# Relay_Output.net
KiCad netlist of a schematic drawn in Altium Designer
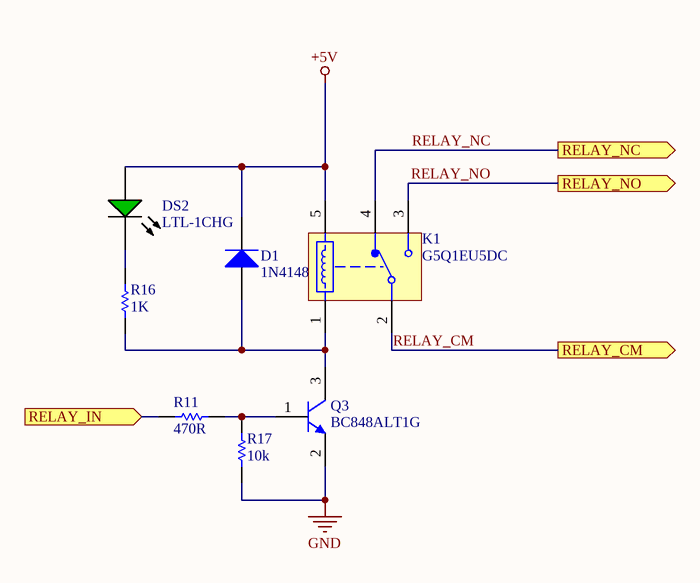
[diagram p0: Relay Output.SchDoc]

(export (version "E")
  (design (tool "Eeschema 10.0.6"))
  (components
    (comp (ref "D1")
      (value "1N4148WT")
      (footprint "FAIR-SOD-523F-2_V")
      (description "High Conductance Fast Switching Diode, 75 V, -55 to 150 degC, 2-Pin SOD523F, RoHS")
      (fields (field (name "MANUFACTURER") "Fairchild Semiconductor"))
      (libsource (lib "Altium Content Vault") (part "FAIR-D_K1A2-2"))
    )
    (comp (ref "DS2")
      (value "LTL-1CHG")
      (footprint "LTST-LTL-1CHG-2")
      (description "LITE-ON Electronic, INC, 120 mA, 100 mW, 5 V, -55 to 100 degC, 2-Pin THD, RoHS, Bulk")
      (libsource (lib "Altium Content Vault") (part "LED_GREEN_A1K2-2"))
    )
    (comp (ref "K1")
      (value "G5Q1EU5DC")
      (footprint "G5Q1EU5DC")
      (description "OMRON - G5Q-1EU 5DC - RELAY, SPDT, 250VAC, 30VDC, 10A")
      (libsource (lib "cpd") (part "G5Q1EU5DC"))
    )
    (comp (ref "Q3")
      (value "BC848ALT1G")
      (footprint "ONSC-SOT-23-3-318-08_V")
      (description "General Purpose Transistor, NPN Silicon, 3-Pin SOT-23, Pb-Free, Tape and Reel")
      (fields (field (name "MANUFACTURER") "On Semiconductor"))
      (libsource (lib "Altium Content Vault") (part "ONSC-NPN-B1E2C3-3"))
    )
    (comp (ref "R11")
      (value "470R")
      (footprint "RESC0603(1608)_M")
      (description "470R 0.1W 1% 0603 (1608 Metric)  SMD")
      (fields (field (name "POWER") "0.1 W") (field (name "TOLERANCE") "1 %"))
      (libsource (lib "Altium Content Vault") (part "RES"))
    )
    (comp (ref "R16")
      (value "1K")
      (footprint "RESC1608X55X30LL15T15")
      (fields (field (name "PART NUMBER") "ERJ-3EKF1001V") (field (name "MANUFACTURER") "Panasonic"))
      (libsource (lib "Altium Content Vault") (part "RES"))
    )
    (comp (ref "R17")
      (value "10k")
      (footprint "RESC1609X55X30LL15T15")
      (description "Chip Resistor, 10 KOhm, +/- 1%, 0.1 W, -55 to 155 degC, 0603 (1608 Metric), RoHS, Tape and Reel")
      (fields (field (name "TOLERANCE") "1%") (field (name "MANUFACTURER") "Panasonic"))
      (libsource (lib "Altium Content Vault") (part "RES-2"))
    )
  )
  (nets
    (net (code "1") (name "+5V") (class "Default")
      (node (ref "D1") (pin "1") (pinfunction "K_1") (pintype "passive"))
      (node (ref "DS2") (pin "1") (pinfunction "A_1") (pintype "passive"))
      (node (ref "K1") (pin "5") (pinfunction "5_5") (pintype "passive"))
    )
    (net (code "2") (name "/RELAY_CM") (class "Default")
      (node (ref "K1") (pin "2") (pinfunction "2_2") (pintype "passive"))
    )
    (net (code "3") (name "/RELAY_IN") (class "Default")
      (node (ref "R11") (pin "1") (pinfunction "1_1") (pintype "passive"))
    )
    (net (code "4") (name "/RELAY_NC") (class "Default")
      (node (ref "K1") (pin "4") (pinfunction "4_4") (pintype "passive"))
    )
    (net (code "5") (name "/RELAY_NO") (class "Default")
      (node (ref "K1") (pin "3") (pinfunction "3_3") (pintype "passive"))
    )
    (net (code "6") (name "GND") (class "Default")
      (node (ref "Q3") (pin "2") (pinfunction "E_2") (pintype "passive"))
      (node (ref "R17") (pin "1") (pinfunction "1_1") (pintype "passive"))
    )
    (net (code "7") (name "Net-(D1-A)") (class "Default")
      (node (ref "D1") (pin "2") (pinfunction "A_2") (pintype "passive"))
      (node (ref "K1") (pin "1") (pinfunction "1_1") (pintype "passive"))
      (node (ref "Q3") (pin "3") (pinfunction "C_3") (pintype "passive"))
      (node (ref "R16") (pin "1") (pinfunction "1_1") (pintype "passive"))
    )
    (net (code "8") (name "Net-(DS2-K)") (class "Default")
      (node (ref "DS2") (pin "2") (pinfunction "K_2") (pintype "passive"))
      (node (ref "R16") (pin "2") (pinfunction "2_2") (pintype "passive"))
    )
    (net (code "9") (name "Net-(Q3-B)") (class "Default")
      (node (ref "Q3") (pin "1") (pinfunction "B_1") (pintype "passive"))
      (node (ref "R11") (pin "2") (pinfunction "2_2") (pintype "passive"))
      (node (ref "R17") (pin "2") (pinfunction "2_2") (pintype "passive"))
    )
  )
)
